# MCU.net
KiCad netlist of a schematic drawn in Altium Designer
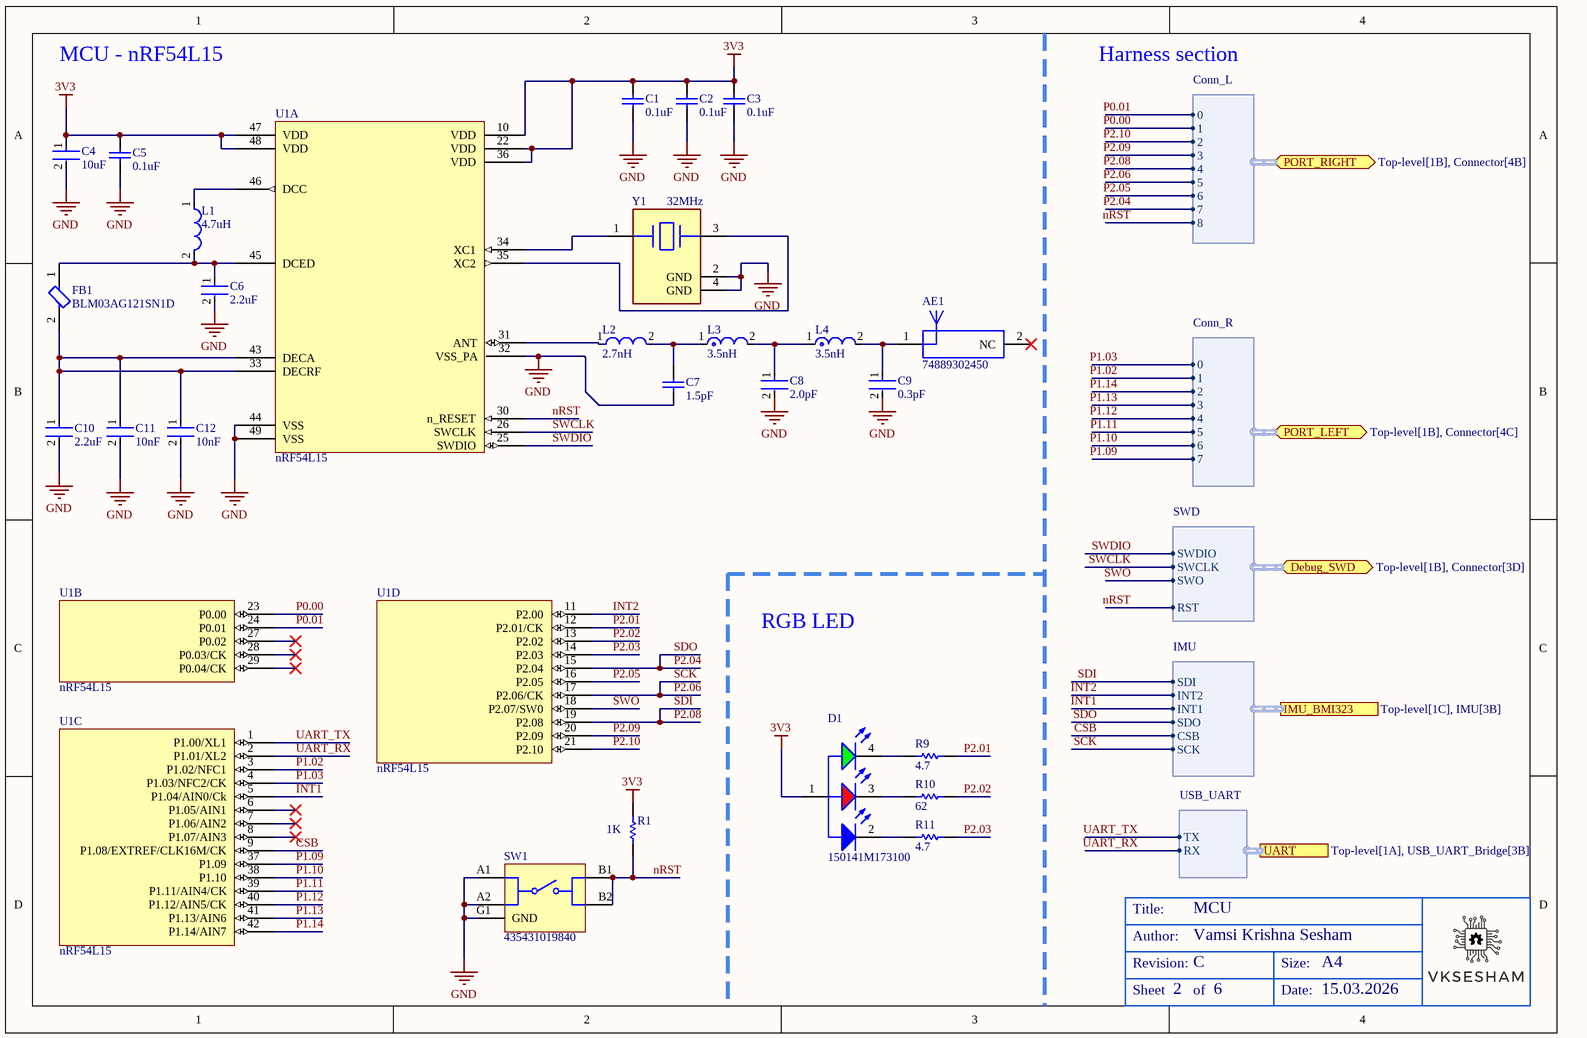
[diagram p0: MCU.SchDoc]

(export (version "E")
  (design (tool "Eeschema 10.0.6"))
  (components
    (comp (ref "AE1")
      (value "74889302450")
      (footprint "74889302450")
      (description "74889302450 Chip Antenna, 2.45Ghz, 3.2Mm X 1.6Mm X 1.2Mm Rohs Compliant: Yes")
      (libsource (lib "Altium Content Vault") (part "74889302450"))
    )
    (comp (ref "C1")
      (value "0.1uF")
      (footprint "CAPC0603X33X15ML03T05")
      (fields (field (name "MANUFACTURER") "Samsung") (field (name "PART NUMBER") "CL03A104KQ3NNNC"))
      (libsource (lib "Altium Content Vault") (part "CAP"))
    )
    (comp (ref "C2")
      (value "0.1uF")
      (footprint "CAPC0603X33X15ML03T05")
      (fields (field (name "MANUFACTURER") "Samsung") (field (name "PART NUMBER") "CL03A104KQ3NNNC"))
      (libsource (lib "Altium Content Vault") (part "CAP"))
    )
    (comp (ref "C3")
      (value "0.1uF")
      (footprint "CAPC0603X33X15ML03T05")
      (fields (field (name "MANUFACTURER") "Samsung") (field (name "PART NUMBER") "CL03A104KQ3NNNC"))
      (libsource (lib "Altium Content Vault") (part "CAP"))
    )
    (comp (ref "C4")
      (value "10uF")
      (footprint "FP-CL07-IPC_C")
      (description "Cap Ceramic 10uF 10V X5R ±20% SMD 0402 +85°C Paper T/R")
      (fields (field (name "TOLERANCE") "20%"))
      (libsource (lib "Altium Content Vault") (part "b4654b650e69147ec39a6b967a45e02"))
    )
    (comp (ref "C5")
      (value "0.1uF")
      (footprint "CAPC0603X33X15ML03T05")
      (fields (field (name "MANUFACTURER") "Samsung") (field (name "PART NUMBER") "CL03A104KQ3NNNC"))
      (libsource (lib "Altium Content Vault") (part "CAP"))
    )
    (comp (ref "C6")
      (value "2.2uF")
      (footprint "FP-CL03-IPC_B")
      (description "Cap Ceramic 2.2uF 10V X5R ±20% Pad SMD 0201 +85°C T/R")
      (fields (field (name "TOLERANCE") "20%"))
      (libsource (lib "Altium Content Vault") (part "b4654b650e69147ec39a6b967a45e02"))
    )
    (comp (ref "C7")
      (value "1.5pF")
      (footprint "CAPC0603X33X15NL03T05")
      (fields
        (field (name "PART NUMBER") "02013A1R5CAT2A")
        (field (name "MANUFACTURER") "AVX Interconnect / Elco")
      )
      (libsource (lib "Altium Content Vault") (part "CAP"))
    )
    (comp (ref "C8")
      (value "2.0pF")
      (footprint "FP-GRM033-0_03-MFG")
      (description "Chip Multilayer Ceramic Capacitors for General Purpose, 0201, 2.0pF, C0G, 30ppm/°C, 0.25pF, 25V")
      (libsource (lib "Altium Content Vault") (part "b4654b650e69147ec39a6b967a45e02"))
    )
    (comp (ref "C9")
      (value "0.3pF")
      (footprint "FP-GJM033-0_03-IPC_A")
      (description "Ceramic Capacitor 0.3pF ±0.05pF 25V C0G 0201 (0603 Metric)")
      (libsource (lib "Altium Content Vault") (part "b4654b650e69147ec39a6b967a45e02"))
    )
    (comp (ref "C10")
      (value "2.2uF")
      (footprint "FP-CL03-IPC_B")
      (description "Cap Ceramic 2.2uF 10V X5R ±20% Pad SMD 0201 +85°C T/R")
      (fields (field (name "TOLERANCE") "20%"))
      (libsource (lib "Altium Content Vault") (part "b4654b650e69147ec39a6b967a45e02"))
    )
    (comp (ref "C11")
      (value "10nF")
      (footprint "FP-GRM033-0_03-IPC_B")
      (description "Chip Multilayer Ceramic Capacitors for General Purpose, 0201, 10000pF, X7R, 15%, 10%, 10V")
      (fields (field (name "VOLTAGE") "10V") (field (name "TOLERANCE") "10%"))
      (libsource (lib "Altium Content Vault") (part "b4654b650e69147ec39a6b967a45e02"))
    )
    (comp (ref "C12")
      (value "10nF")
      (footprint "FP-GRM033-0_03-IPC_B")
      (description "Chip Multilayer Ceramic Capacitors for General Purpose, 0201, 10000pF, X7R, 15%, 10%, 10V")
      (fields (field (name "VOLTAGE") "10V") (field (name "TOLERANCE") "10%"))
      (libsource (lib "Altium Content Vault") (part "b4654b650e69147ec39a6b967a45e02"))
    )
    (comp (ref "D1")
      (value "150141M173100")
      (footprint "WL-SFTW_3528_150141M173100")
      (libsource (lib "Altium Content Vault") (part "WL-SFTW_150141M173100"))
    )
    (comp (ref "FB1")
      (value "BLM03AG121SN1D")
      (footprint "FP-BLM03-0_03-d0_3-IPC_A")
      (description "Ferrite Bead, 0201, 120Ω @ 100MHz, 25%, 0.5Ω, 200mA")
      (fields (field (name "TOLERANCE") "25%"))
      (libsource (lib "Altium Content Vault") (part "5f30dd21d616792df468990f7003faa"))
    )
    (comp (ref "L1")
      (value "4.7uH")
      (footprint "FP-MLZ1608-IPC_A")
      (description "Shielded Multilayer Inductor 4.7uH ±20% 350mA 650mΩ SMD 0603")
      (fields (field (name "TOLERANCE") "20%"))
      (libsource (lib "Altium Content Vault") (part "725321dda6339637d4d059423bc1c3c"))
    )
    (comp (ref "L2")
      (value "2.7nH")
      (footprint "FP-LQP03HQ_02-MFG")
      (description "Film type RF Inductor 2.7nH ±0.1nH 600mA 0.12Ω 0201 (0603)")
      (libsource (lib "Altium Content Vault") (part "725321dda6339637d4d059423bc1c3c"))
    )
    (comp (ref "L3")
      (value "3.5nH")
      (footprint "FP-LQP03TG_02-IPC_C")
      (description "Film type RF Inductor 3.5nH ±0.1nH 450mA 0.25Ω 0201 (0603)")
      (libsource (lib "Altium Content Vault") (part "4cc4b267dca4c8e51f7102f422741d8"))
    )
    (comp (ref "L4")
      (value "3.5nH")
      (footprint "FP-LQP03TG_02-IPC_C")
      (description "Film type RF Inductor 3.5nH ±0.1nH 450mA 0.25Ω 0201 (0603)")
      (libsource (lib "Altium Content Vault") (part "4cc4b267dca4c8e51f7102f422741d8"))
    )
    (comp (ref "R1")
      (value "1K")
      (footprint "RESC0603X28X15ML05T05")
      (fields (field (name "MANUFACTURER") "Vishay Dale") (field (name "PART NUMBER") "CRCW02011K00FNED"))
      (libsource (lib "Altium Content Vault") (part "RES"))
    )
    (comp (ref "R9")
      (value "4.7")
      (footprint "RESC0402(1005)_M")
      (description "4R7 0.063W 5% 0402 (1005 Metric)  SMD")
      (fields (field (name "POWER") "0.063 W") (field (name "TOLERANCE") "5 %"))
      (libsource (lib "Altium Content Vault") (part "RES"))
    )
    (comp (ref "R10")
      (value "62")
      (footprint "RESC1005X40X25LL05T05")
      (fields (field (name "PART NUMBER") "CRCW040262R0JNED") (field (name "MANUFACTURER") "Vishay Dale"))
      (libsource (lib "Altium Content Vault") (part "RES"))
    )
    (comp (ref "R11")
      (value "4.7")
      (footprint "RESC0402(1005)_M")
      (description "4R7 0.063W 5% 0402 (1005 Metric)  SMD")
      (fields (field (name "POWER") "0.063 W") (field (name "TOLERANCE") "5 %"))
      (libsource (lib "Altium Content Vault") (part "RES"))
    )
    (comp (ref "SW1")
      (value "435431019840")
      (footprint "435431019840")
      (description "Tactile Switch, 0.05A, 32VDC, SMD, 400GF Rohs Compliant: Yes")
      (libsource (lib "Altium Content Vault") (part "SPST-NO_4P_1GND"))
    )
    (comp (ref "U1")
      (value "nRF54L15")
      (footprint "nRF54L15_QFN8_6X6")
      (description "Ultra-low-power wireless SoC")
      (libsource (lib "") (part "nRF54L15_QFN8_6X6_1"))
    )
    (comp (ref "Y1")
      (value "32MHz")
      (footprint "FP-ABM8G-MFG")
      (description "Crystal 32MHz ±30ppm (Tol) ±30ppm (Stability) 10pF FUND 50Ω 4-Pin SMD T/R")
      (fields (field (name "TOLERANCE") "30ppm"))
      (libsource (lib "Altium Content Vault") (part "48e526d86b7f2615d98721063c72f49"))
    )
  )
  (nets
    (net (code "6") (name "/CSB") (class "Default")
      (node (ref "U1") (pin "9") (pinfunction "P1.08/EXTREF/CLK16M/CK_9") (pintype "bidirectional"))
    )
    (net (code "7") (name "/INT1") (class "Default")
      (node (ref "U1") (pin "5") (pinfunction "P1.04/AIN0/Ck_5") (pintype "bidirectional"))
    )
    (net (code "8") (name "/INT2") (class "Default")
      (node (ref "U1") (pin "11") (pinfunction "P2.00_11") (pintype "bidirectional"))
    )
    (net (code "9") (name "/P0.00") (class "Default")
      (node (ref "U1") (pin "23") (pinfunction "P0.00_23") (pintype "bidirectional"))
    )
    (net (code "10") (name "/P0.01") (class "Default")
      (node (ref "U1") (pin "24") (pinfunction "P0.01_24") (pintype "bidirectional"))
    )
    (net (code "11") (name "/P1.02") (class "Default")
      (node (ref "U1") (pin "3") (pinfunction "P1.02/NFC1_3") (pintype "bidirectional"))
    )
    (net (code "12") (name "/P1.03") (class "Default")
      (node (ref "U1") (pin "4") (pinfunction "P1.03/NFC2/CK_4") (pintype "bidirectional"))
    )
    (net (code "13") (name "/P1.09") (class "Default")
      (node (ref "U1") (pin "37") (pinfunction "P1.09_37") (pintype "bidirectional"))
    )
    (net (code "14") (name "/P1.10") (class "Default")
      (node (ref "U1") (pin "38") (pinfunction "P1.10_38") (pintype "bidirectional"))
    )
    (net (code "15") (name "/P1.11") (class "Default")
      (node (ref "U1") (pin "39") (pinfunction "P1.11/AIN4/CK_39") (pintype "bidirectional"))
    )
    (net (code "16") (name "/P1.12") (class "Default")
      (node (ref "U1") (pin "40") (pinfunction "P1.12/AIN5/CK_40") (pintype "bidirectional"))
    )
    (net (code "17") (name "/P1.13") (class "Default")
      (node (ref "U1") (pin "41") (pinfunction "P1.13/AIN6_41") (pintype "bidirectional"))
    )
    (net (code "18") (name "/P1.14") (class "Default")
      (node (ref "U1") (pin "42") (pinfunction "P1.14/AIN7_42") (pintype "bidirectional"))
    )
    (net (code "19") (name "/P2.01") (class "Default")
      (node (ref "R9") (pin "2") (pinfunction "2_2") (pintype "passive"))
      (node (ref "U1") (pin "12") (pinfunction "P2.01/CK_12") (pintype "bidirectional"))
    )
    (net (code "20") (name "/P2.02") (class "Default")
      (node (ref "R10") (pin "2") (pinfunction "2_2") (pintype "passive"))
      (node (ref "U1") (pin "13") (pinfunction "P2.02_13") (pintype "bidirectional"))
    )
    (net (code "21") (name "/P2.03") (class "Default")
      (node (ref "R11") (pin "2") (pinfunction "2_2") (pintype "passive"))
      (node (ref "U1") (pin "14") (pinfunction "P2.03_14") (pintype "bidirectional"))
    )
    (net (code "22") (name "/P2.04") (class "Default")
      (node (ref "U1") (pin "15") (pinfunction "P2.04_15") (pintype "bidirectional"))
    )
    (net (code "23") (name "/P2.05") (class "Default")
      (node (ref "U1") (pin "16") (pinfunction "P2.05_16") (pintype "bidirectional"))
    )
    (net (code "24") (name "/P2.06") (class "Default")
      (node (ref "U1") (pin "17") (pinfunction "P2.06/CK_17") (pintype "bidirectional"))
    )
    (net (code "25") (name "/P2.08") (class "Default")
      (node (ref "U1") (pin "19") (pinfunction "P2.08_19") (pintype "bidirectional"))
    )
    (net (code "26") (name "/P2.09") (class "Default")
      (node (ref "U1") (pin "20") (pinfunction "P2.09_20") (pintype "bidirectional"))
    )
    (net (code "27") (name "/P2.10") (class "Default")
      (node (ref "U1") (pin "21") (pinfunction "P2.10_21") (pintype "bidirectional"))
    )
    (net (code "28") (name "/SWCLK") (class "Default")
      (node (ref "U1") (pin "26") (pinfunction "SWCLK_26") (pintype "input"))
    )
    (net (code "29") (name "/SWDIO") (class "Default")
      (node (ref "U1") (pin "25") (pinfunction "SWDIO_25") (pintype "bidirectional"))
    )
    (net (code "30") (name "/SWO") (class "Default")
      (node (ref "U1") (pin "18") (pinfunction "P2.07/SW0_18") (pintype "bidirectional"))
    )
    (net (code "31") (name "/UART_RX") (class "Default")
      (node (ref "U1") (pin "2") (pinfunction "P1.01/XL2_2") (pintype "bidirectional"))
    )
    (net (code "32") (name "/UART_TX") (class "Default")
      (node (ref "U1") (pin "1") (pinfunction "P1.00/XL1_1") (pintype "bidirectional"))
    )
    (net (code "33") (name "/nRST") (class "Default")
      (node (ref "R1") (pin "1") (pinfunction "1_1") (pintype "passive"))
      (node (ref "SW1") (pin "B1") (pinfunction "B1_B1") (pintype "passive"))
      (node (ref "SW1") (pin "B2") (pinfunction "B2_B2") (pintype "passive"))
      (node (ref "U1") (pin "30") (pinfunction "n_RESET_30") (pintype "input"))
    )
    (net (code "39") (name "3V3") (class "Default")
      (node (ref "C1") (pin "2") (pinfunction "2_2") (pintype "passive"))
      (node (ref "C2") (pin "2") (pinfunction "2_2") (pintype "passive"))
      (node (ref "C3") (pin "2") (pinfunction "2_2") (pintype "passive"))
      (node (ref "C4") (pin "1") (pinfunction "1_1") (pintype "passive"))
      (node (ref "C5") (pin "2") (pinfunction "2_2") (pintype "passive"))
      (node (ref "D1") (pin "1") (pinfunction "A_1") (pintype "passive"))
      (node (ref "R1") (pin "2") (pinfunction "2_2") (pintype "passive"))
      (node (ref "U1") (pin "10") (pinfunction "VDD_10") (pintype "power_in"))
      (node (ref "U1") (pin "22") (pinfunction "VDD_22") (pintype "power_in"))
      (node (ref "U1") (pin "36") (pinfunction "VDD_36") (pintype "power_in"))
      (node (ref "U1") (pin "47") (pinfunction "VDD_47") (pintype "power_in"))
      (node (ref "U1") (pin "48") (pinfunction "VDD_48") (pintype "power_in"))
    )
    (net (code "40") (name "GND") (class "Default")
      (node (ref "C1") (pin "1") (pinfunction "1_1") (pintype "passive"))
      (node (ref "C10") (pin "2") (pinfunction "2_2") (pintype "passive"))
      (node (ref "C11") (pin "2") (pinfunction "2_2") (pintype "passive"))
      (node (ref "C12") (pin "2") (pinfunction "2_2") (pintype "passive"))
      (node (ref "C2") (pin "1") (pinfunction "1_1") (pintype "passive"))
      (node (ref "C3") (pin "1") (pinfunction "1_1") (pintype "passive"))
      (node (ref "C4") (pin "2") (pinfunction "2_2") (pintype "passive"))
      (node (ref "C5") (pin "1") (pinfunction "1_1") (pintype "passive"))
      (node (ref "C6") (pin "2") (pinfunction "2_2") (pintype "passive"))
      (node (ref "C7") (pin "1") (pinfunction "1_1") (pintype "passive"))
      (node (ref "C8") (pin "2") (pinfunction "2_2") (pintype "passive"))
      (node (ref "C9") (pin "2") (pinfunction "2_2") (pintype "passive"))
      (node (ref "SW1") (pin "A1") (pinfunction "A1_A1") (pintype "passive"))
      (node (ref "SW1") (pin "A2") (pinfunction "A2_A2") (pintype "passive"))
      (node (ref "SW1") (pin "G1") (pinfunction "GND_G1") (pintype "passive"))
      (node (ref "U1") (pin "32") (pinfunction "VSS_PA_32") (pintype "power_in"))
      (node (ref "U1") (pin "44") (pinfunction "VSS_44") (pintype "power_in"))
      (node (ref "U1") (pin "49") (pinfunction "VSS_49") (pintype "power_in"))
      (node (ref "Y1") (pin "2") (pinfunction "GND_2") (pintype "power_in"))
      (node (ref "Y1") (pin "4") (pinfunction "GND_4") (pintype "power_in"))
    )
    (net (code "41") (name "Net-(AE1-Feed)") (class "Default")
      (node (ref "AE1") (pin "1") (pinfunction "Feed_1") (pintype "passive"))
      (node (ref "C9") (pin "1") (pinfunction "1_1") (pintype "passive"))
      (node (ref "L4") (pin "2") (pinfunction "2_2") (pintype "passive"))
    )
    (net (code "42") (name "Net-(C7-Pad2)") (class "Default")
      (node (ref "C7") (pin "2") (pinfunction "2_2") (pintype "passive"))
      (node (ref "L2") (pin "2") (pinfunction "2_2") (pintype "passive"))
      (node (ref "L3") (pin "1") (pinfunction "1_1") (pintype "passive"))
    )
    (net (code "43") (name "Net-(C8-Pad1)") (class "Default")
      (node (ref "C8") (pin "1") (pinfunction "1_1") (pintype "passive"))
      (node (ref "L3") (pin "2") (pinfunction "2_2") (pintype "passive"))
      (node (ref "L4") (pin "1") (pinfunction "1_1") (pintype "passive"))
    )
    (net (code "44") (name "Net-(D1-K-Pad2)") (class "Default")
      (node (ref "D1") (pin "2") (pinfunction "K_2") (pintype "passive"))
      (node (ref "R11") (pin "1") (pinfunction "1_1") (pintype "passive"))
    )
    (net (code "45") (name "Net-(D1-K-Pad3)") (class "Default")
      (node (ref "D1") (pin "3") (pinfunction "K_3") (pintype "passive"))
      (node (ref "R10") (pin "1") (pinfunction "1_1") (pintype "passive"))
    )
    (net (code "46") (name "Net-(D1-K-Pad4)") (class "Default")
      (node (ref "D1") (pin "4") (pinfunction "K_4") (pintype "passive"))
      (node (ref "R9") (pin "1") (pinfunction "1_1") (pintype "passive"))
    )
    (net (code "47") (name "Net-(U1A-ANT)") (class "Default")
      (node (ref "L2") (pin "1") (pinfunction "1_1") (pintype "passive"))
      (node (ref "U1") (pin "31") (pinfunction "ANT_31") (pintype "bidirectional"))
    )
    (net (code "48") (name "Net-(U1A-DCC)") (class "Default")
      (node (ref "L1") (pin "1") (pinfunction "1_1") (pintype "passive"))
      (node (ref "U1") (pin "46") (pinfunction "DCC_46") (pintype "output"))
    )
    (net (code "49") (name "Net-(U1A-DCED)") (class "Default")
      (node (ref "C6") (pin "1") (pinfunction "1_1") (pintype "passive"))
      (node (ref "FB1") (pin "1") (pinfunction "1_1") (pintype "passive"))
      (node (ref "L1") (pin "2") (pinfunction "2_2") (pintype "passive"))
      (node (ref "U1") (pin "45") (pinfunction "DCED_45") (pintype "power_in"))
    )
    (net (code "50") (name "Net-(U1A-DECA)") (class "Default")
      (node (ref "C10") (pin "1") (pinfunction "1_1") (pintype "passive"))
      (node (ref "C11") (pin "1") (pinfunction "1_1") (pintype "passive"))
      (node (ref "C12") (pin "1") (pinfunction "1_1") (pintype "passive"))
      (node (ref "FB1") (pin "2") (pinfunction "2_2") (pintype "passive"))
      (node (ref "U1") (pin "33") (pinfunction "DECRF_33") (pintype "power_in"))
      (node (ref "U1") (pin "43") (pinfunction "DECA_43") (pintype "power_in"))
    )
    (net (code "51") (name "Net-(U1A-XC1)") (class "Default")
      (node (ref "U1") (pin "34") (pinfunction "XC1_34") (pintype "input"))
      (node (ref "Y1") (pin "1") (pinfunction "1_1") (pintype "passive"))
    )
    (net (code "52") (name "Net-(U1A-XC2)") (class "Default")
      (node (ref "U1") (pin "35") (pinfunction "XC2_35") (pintype "output"))
      (node (ref "Y1") (pin "3") (pinfunction "3_3") (pintype "passive"))
    )
    (net (code "53") (name "unconnected-(AE1-NC-Pad2)") (class "Default")
      (node (ref "AE1") (pin "2") (pinfunction "NC_2") (pintype "passive+no_connect"))
    )
    (net (code "54") (name "unconnected-(U1B-P0.02-Pad27)") (class "Default")
      (node (ref "U1") (pin "27") (pinfunction "P0.02_27") (pintype "bidirectional+no_connect"))
    )
    (net (code "55") (name "unconnected-(U1B-P0.03{slash}CK-Pad28)") (class "Default")
      (node (ref "U1") (pin "28") (pinfunction "P0.03/CK_28") (pintype "bidirectional+no_connect"))
    )
    (net (code "56") (name "unconnected-(U1B-P0.04{slash}CK-Pad29)") (class "Default")
      (node (ref "U1") (pin "29") (pinfunction "P0.04/CK_29") (pintype "bidirectional+no_connect"))
    )
    (net (code "57") (name "unconnected-(U1C-P1.05{slash}AIN1-Pad6)") (class "Default")
      (node (ref "U1") (pin "6") (pinfunction "P1.05/AIN1_6") (pintype "bidirectional+no_connect"))
    )
    (net (code "58") (name "unconnected-(U1C-P1.06{slash}AIN2-Pad7)") (class "Default")
      (node (ref "U1") (pin "7") (pinfunction "P1.06/AIN2_7") (pintype "bidirectional+no_connect"))
    )
    (net (code "59") (name "unconnected-(U1C-P1.07{slash}AIN3-Pad8)") (class "Default")
      (node (ref "U1") (pin "8") (pinfunction "P1.07/AIN3_8") (pintype "bidirectional+no_connect"))
    )
  )
)
